# Env_sensor_v1_0.net
KiCad netlist of a schematic drawn in EAGLE
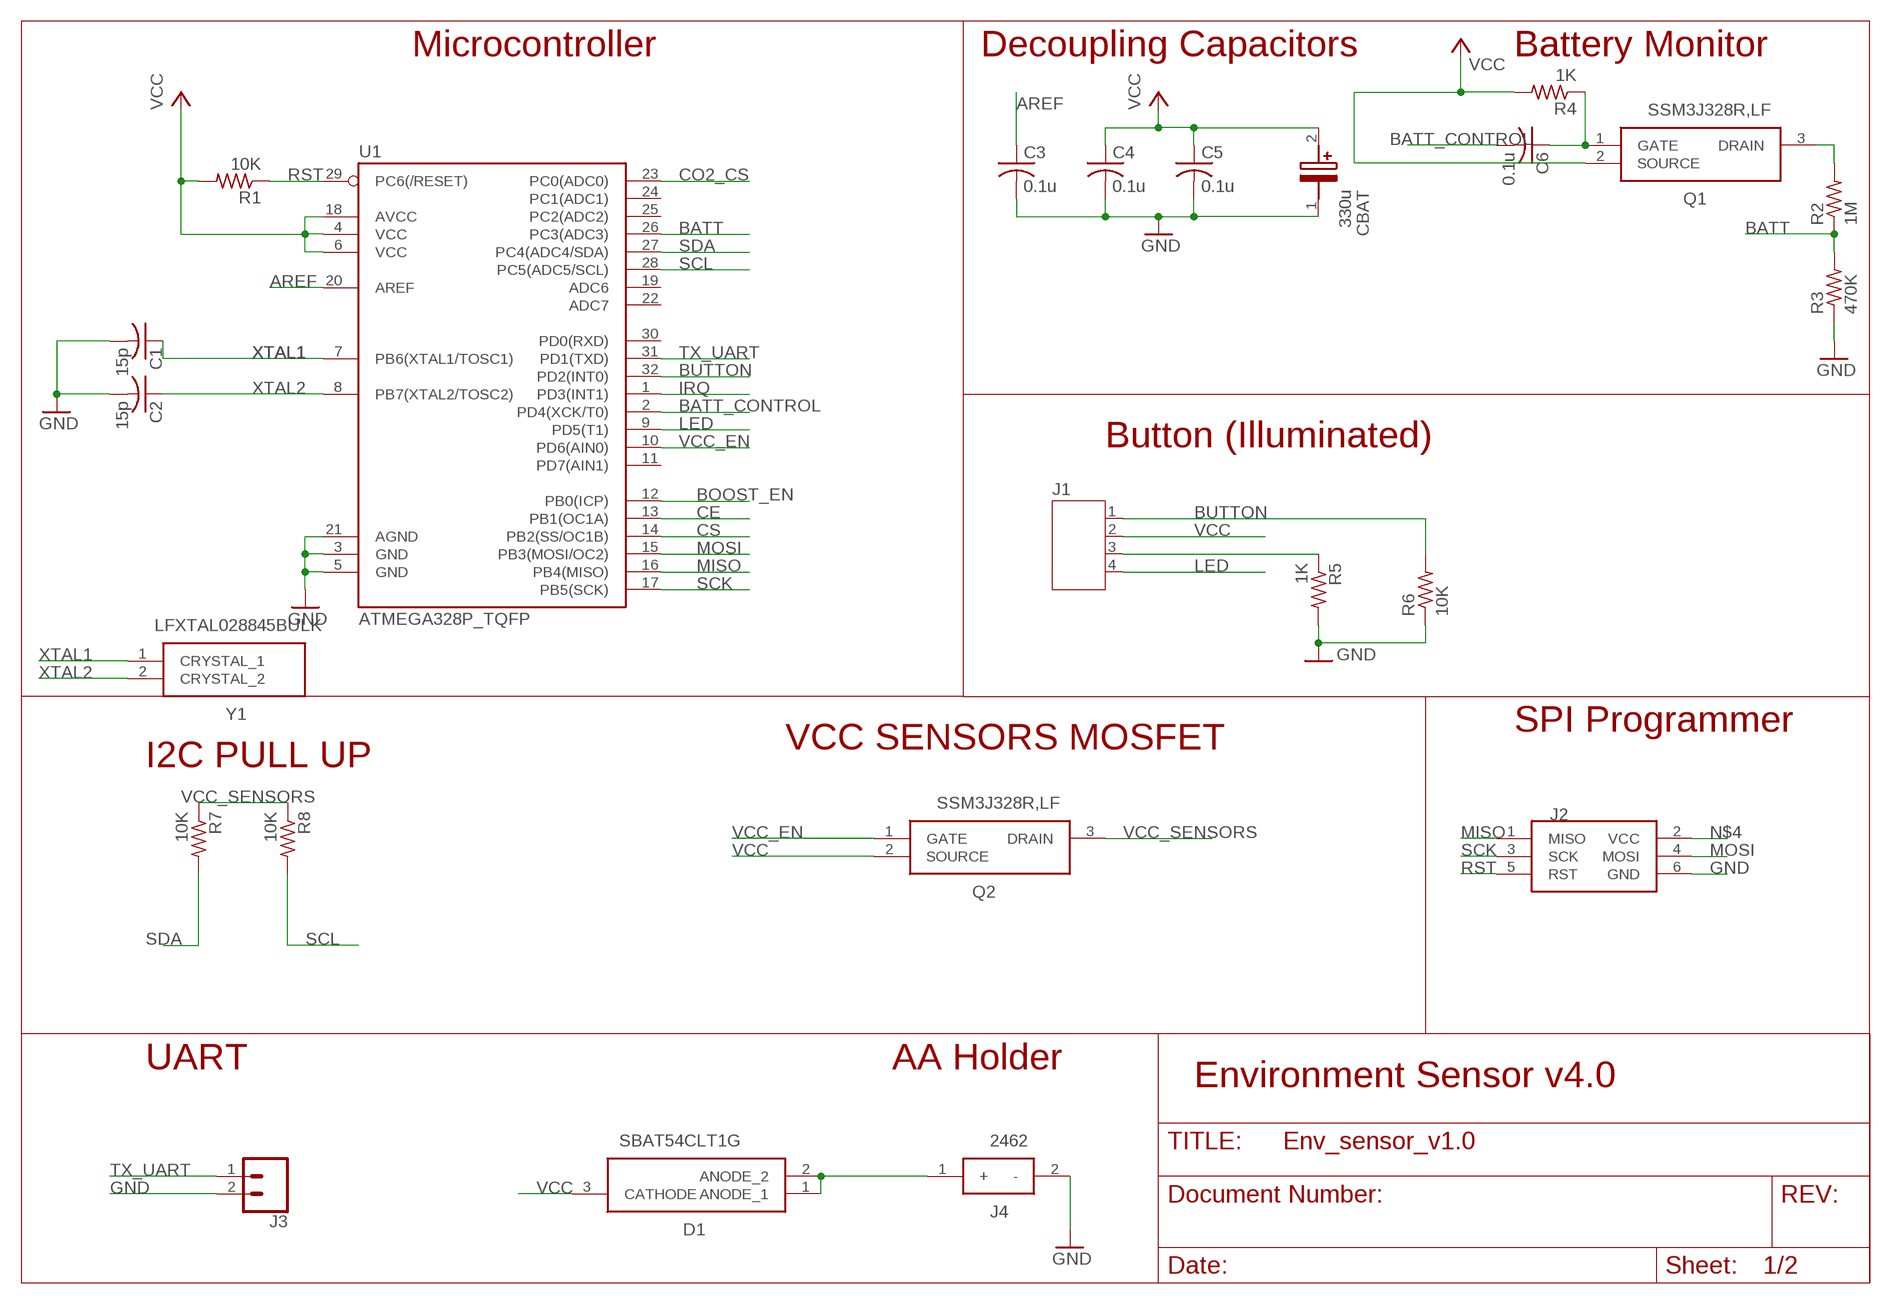
[diagram p0: schematic, sheet 1]
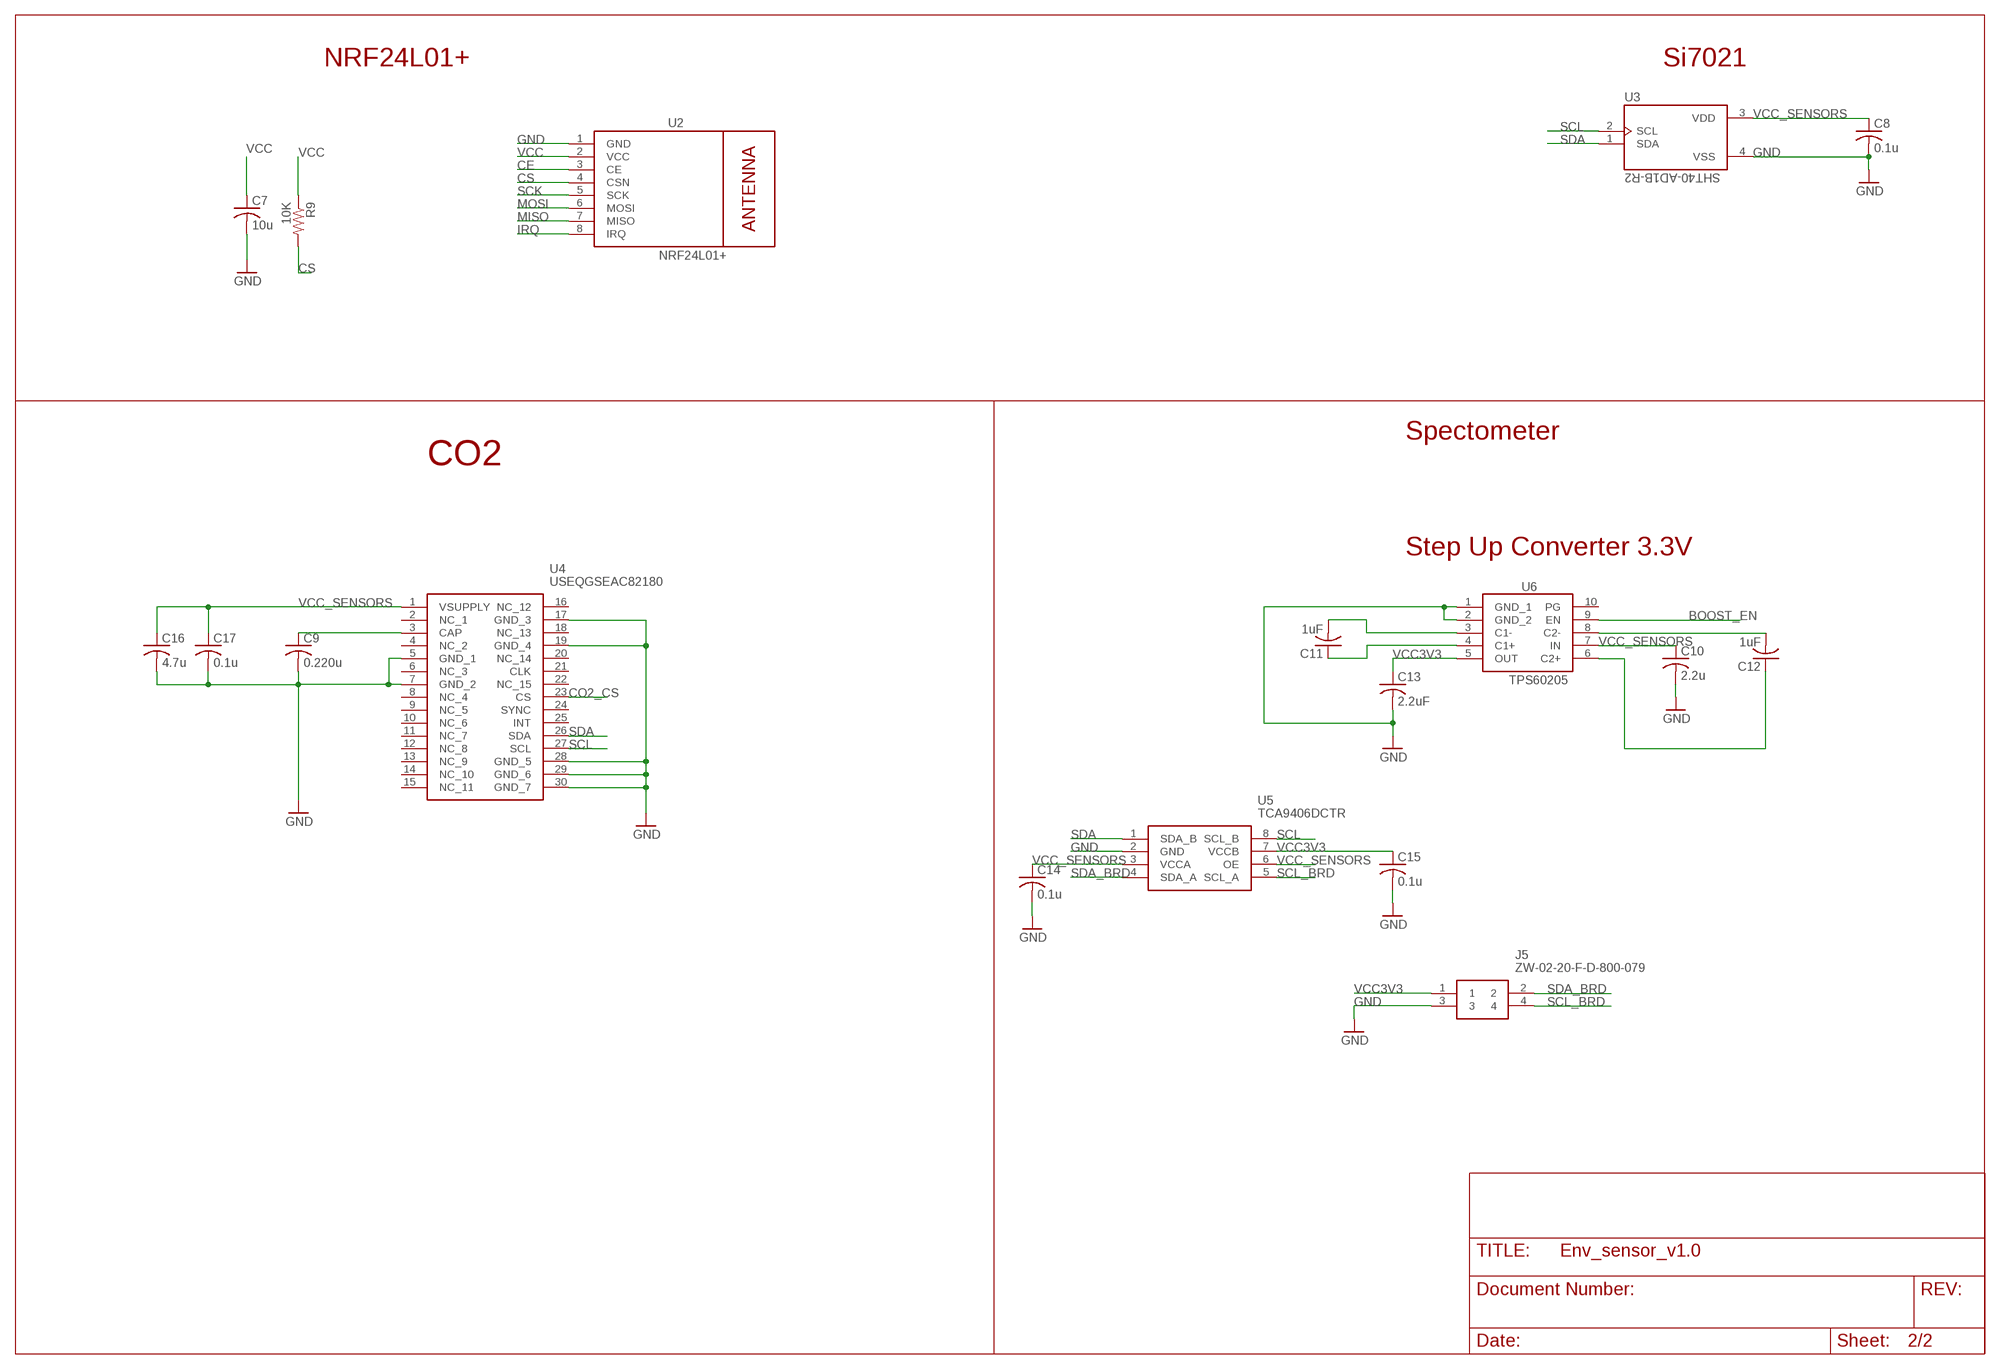
[diagram p1: schematic, sheet 2]

(export (version "E")
  (design (tool "Eeschema 10.0.6"))
  (components
    (comp (ref "C1")
      (value "15p")
      (footprint "eagle-import:SMD-0805")
      (libsource (lib "eagle-import") (part "CAPACITOR-SMD-0805"))
    )
    (comp (ref "C2")
      (value "15p")
      (footprint "eagle-import:SMD-0805")
      (libsource (lib "eagle-import") (part "CAPACITOR-SMD-0805"))
    )
    (comp (ref "C3")
      (value "0.1u")
      (footprint "eagle-import:SMD-0805")
      (libsource (lib "eagle-import") (part "CAPACITOR-SMD-0805"))
    )
    (comp (ref "C4")
      (value "0.1u")
      (footprint "eagle-import:SMD-0805")
      (libsource (lib "eagle-import") (part "CAPACITOR-SMD-0805"))
    )
    (comp (ref "C5")
      (value "0.1u")
      (footprint "eagle-import:SMD-0805")
      (libsource (lib "eagle-import") (part "CAPACITOR-SMD-0805"))
    )
    (comp (ref "C6")
      (value "0.1u")
      (footprint "eagle-import:SMD-0805")
      (libsource (lib "eagle-import") (part "CAPACITOR-SMD-0805"))
    )
    (comp (ref "CBAT")
      (value "330u")
      (footprint "eagle-import:SMD_LYTIC_D8")
      (fields
        (field (name "MANUFACTURER_PART_NUMBER") "EEE-FNC271XUP")
        (field (name "MOUSER_PART_NUMBER") "667-EEE-FNC271XUP")
      )
      (libsource (lib "eagle-import") (part "EEE-FNC271XUP"))
    )
    (comp (ref "D1")
      (value "SBAT54CLT1G")
      (footprint "eagle-import:SOT96P237X111-3N")
      (fields (field (name "MOUSER_PART_NUMBER") "863-SBAT54CLT1G"))
      (libsource (lib "eagle-import") (part "SBAT54CLT1G"))
    )
    (comp (ref "J1")
      (value "JST-PH4")
      (footprint "eagle-import:JST-PH4")
      (libsource (lib "eagle-import") (part "JST-PH4"))
    )
    (comp (ref "J2")
      (value "ISP")
      (footprint "eagle-import:AVRISP")
      (libsource (lib "eagle-import") (part "AVRISP-6"))
    )
    (comp (ref "J3")
      (value "CONN_02")
      (footprint "eagle-import:1X02")
      (libsource (lib "eagle-import") (part "CONN_02"))
    )
    (comp (ref "J4")
      (value "2462")
      (footprint "eagle-import:2462")
      (fields (field (name "MOUSER_PART_NUMBER") "534-2462"))
      (libsource (lib "eagle-import") (part "2462"))
    )
    (comp (ref "Q1")
      (value "SSM3J328R,LF")
      (footprint "eagle-import:SOTFL95P240X88-3N")
      (fields (field (name "MOUSER_PART_NUMBER") "757-SSM3J328RLF"))
      (libsource (lib "eagle-import") (part "SSM3J328R,LF"))
    )
    (comp (ref "Q2")
      (value "SSM3J328R,LF")
      (footprint "eagle-import:SOTFL95P240X88-3N")
      (fields (field (name "MOUSER_PART_NUMBER") "757-SSM3J328RLF"))
      (libsource (lib "eagle-import") (part "SSM3J328R,LF"))
    )
    (comp (ref "R1")
      (value "10K")
      (footprint "eagle-import:SMD-0805")
      (libsource (lib "eagle-import") (part "RESISTOR-SMD-0805"))
    )
    (comp (ref "R2")
      (value "1M")
      (footprint "eagle-import:SMD-0805")
      (libsource (lib "eagle-import") (part "RESISTOR-SMD-0805"))
    )
    (comp (ref "R3")
      (value "470K")
      (footprint "eagle-import:SMD-0805")
      (libsource (lib "eagle-import") (part "RESISTOR-SMD-0805"))
    )
    (comp (ref "R4")
      (value "1K")
      (footprint "eagle-import:SMD-0805")
      (libsource (lib "eagle-import") (part "RESISTOR-SMD-0805"))
    )
    (comp (ref "R5")
      (value "1K")
      (footprint "eagle-import:SMD-0805")
      (libsource (lib "eagle-import") (part "RESISTOR-SMD-0805"))
    )
    (comp (ref "R6")
      (value "10K")
      (footprint "eagle-import:SMD-0805")
      (libsource (lib "eagle-import") (part "RESISTOR-SMD-0805"))
    )
    (comp (ref "R7")
      (value "10K")
      (footprint "eagle-import:SMD-0805")
      (libsource (lib "eagle-import") (part "RESISTOR-SMD-0805"))
    )
    (comp (ref "R8")
      (value "10K")
      (footprint "eagle-import:SMD-0805")
      (libsource (lib "eagle-import") (part "RESISTOR-SMD-0805"))
    )
    (comp (ref "U1")
      (value "ATMEGA328P_TQFP")
      (footprint "eagle-import:TQFP32-08")
      (libsource (lib "eagle-import") (part "ATMEGA328P_TQFP"))
    )
    (comp (ref "Y1")
      (value "LFXTAL028845BULK")
      (footprint "eagle-import:LFXTAL028845BULK")
      (libsource (lib "eagle-import") (part "LFXTAL028845BULK"))
    )
    (comp (ref "C7")
      (value "10u")
      (footprint "eagle-import:SMD-0805")
      (libsource (lib "eagle-import") (part "CAPACITOR-SMD-0805"))
    )
    (comp (ref "C8")
      (value "0.1u")
      (footprint "eagle-import:SMD-0805")
      (libsource (lib "eagle-import") (part "CAPACITOR-SMD-0805"))
    )
    (comp (ref "C9")
      (value "0.220u")
      (footprint "eagle-import:SMD-0805")
      (libsource (lib "eagle-import") (part "CAPACITOR-SMD-0805"))
    )
    (comp (ref "C10")
      (value "2.2u")
      (footprint "eagle-import:SMD-0805")
      (libsource (lib "eagle-import") (part "CAPACITOR-SMD-0805"))
    )
    (comp (ref "C11")
      (value "1uF")
      (footprint "eagle-import:SMD-0805")
      (libsource (lib "eagle-import") (part "CAPACITOR-SMD-0805"))
    )
    (comp (ref "C12")
      (value "1uF")
      (footprint "eagle-import:SMD-0805")
      (libsource (lib "eagle-import") (part "CAPACITOR-SMD-0805"))
    )
    (comp (ref "C13")
      (value "2.2uF")
      (footprint "eagle-import:SMD-0805")
      (libsource (lib "eagle-import") (part "CAPACITOR-SMD-0805"))
    )
    (comp (ref "C14")
      (value "0.1u")
      (footprint "eagle-import:SMD-0805")
      (libsource (lib "eagle-import") (part "CAPACITOR-SMD-0805"))
    )
    (comp (ref "C15")
      (value "0.1u")
      (footprint "eagle-import:SMD-0805")
      (libsource (lib "eagle-import") (part "CAPACITOR-SMD-0805"))
    )
    (comp (ref "C16")
      (value "4.7u")
      (footprint "eagle-import:SMD-0805")
      (libsource (lib "eagle-import") (part "CAPACITOR-SMD-0805"))
    )
    (comp (ref "C17")
      (value "0.1u")
      (footprint "eagle-import:SMD-0805")
      (libsource (lib "eagle-import") (part "CAPACITOR-SMD-0805"))
    )
    (comp (ref "J5")
      (value "ZW-02-20-F-D-800-079")
      (footprint "eagle-import:HDRV4W64P254_2X2_508X508X2669P")
      (fields (field (name "MOUSER_PART_NUMBER") "200-ZW0220FD800079"))
      (libsource (lib "eagle-import") (part "ZW-02-20-F-D-800-079"))
    )
    (comp (ref "R9")
      (value "10K")
      (footprint "eagle-import:SMD-0805")
      (libsource (lib "eagle-import") (part "RESISTOR-SMD-0805"))
    )
    (comp (ref "U2")
      (value "NRF24L01+")
      (footprint "eagle-import:WIRELESS-NRF24L01")
      (libsource (lib "eagle-import") (part "WIRELESS-NRF24L01"))
    )
    (comp (ref "U3")
      (value "SHT40-AD1B-R2")
      (footprint "eagle-import:XDCR_SHT40-AD1B-R2")
      (fields (field (name "MF") "Sensirion"))
      (libsource (lib "eagle-import") (part "SHT40-AD1B-R2"))
    )
    (comp (ref "U4")
      (value "USEQGSEAC82180")
      (footprint "eagle-import:USEQGSEAC82180")
      (fields (field (name "MOUSER_PART_NUMBER") "80-USEQGSEAC82180"))
      (libsource (lib "eagle-import") (part "USEQGSEAC82180"))
    )
    (comp (ref "U5")
      (value "TCA9406DCTR")
      (footprint "eagle-import:SOP65P400X130-8N")
      (fields (field (name "MOUSER_PART_NUMBER") "595-TCA9406DCTR"))
      (libsource (lib "eagle-import") (part "TCA9406DCTR"))
    )
    (comp (ref "U6")
      (value "TPS60205")
      (footprint "eagle-import:SOP50P488X107-10N")
      (fields
        (field (name "MANUFACTURER_PART_NUMBER") "TPS60205DGSR")
        (field (name "MOUSER_PART_NUMBER") "595-TPS60205DGSR")
      )
      (libsource (lib "eagle-import") (part "TPS60205DGSR"))
    )
  )
  (nets
    (net (code "1") (name "AREF") (class "Default")
      (node (ref "C3") (pin "1") (pinfunction "1_1") (pintype "passive"))
      (node (ref "U1") (pin "20") (pinfunction "AREF_20") (pintype "bidirectional"))
    )
    (net (code "2") (name "BATT") (class "Default")
      (node (ref "R2") (pin "1") (pinfunction "1_1") (pintype "passive"))
      (node (ref "R3") (pin "2") (pinfunction "2_2") (pintype "passive"))
      (node (ref "U1") (pin "26") (pinfunction "PC3(ADC3)_26") (pintype "bidirectional"))
    )
    (net (code "3") (name "BATT_CONTROL") (class "Default")
      (node (ref "C6") (pin "2") (pinfunction "2_2") (pintype "passive"))
      (node (ref "U1") (pin "2") (pinfunction "PD4(XCK/T0)_2") (pintype "bidirectional"))
    )
    (net (code "4") (name "BOOST_EN") (class "Default")
      (node (ref "U1") (pin "12") (pinfunction "PB0(ICP)_12") (pintype "bidirectional"))
      (node (ref "U6") (pin "9") (pinfunction "EN_9") (pintype "bidirectional"))
    )
    (net (code "5") (name "BUTTON") (class "Default")
      (node (ref "J1") (pin "1") (pinfunction "1_1") (pintype "passive"))
      (node (ref "R6") (pin "2") (pinfunction "2_2") (pintype "passive"))
      (node (ref "U1") (pin "32") (pinfunction "PD2(INT0)_32") (pintype "bidirectional"))
    )
    (net (code "6") (name "CE") (class "Default")
      (node (ref "U1") (pin "13") (pinfunction "PB1(OC1A)_13") (pintype "bidirectional"))
      (node (ref "U2") (pin "3") (pinfunction "CE_3") (pintype "bidirectional"))
    )
    (net (code "7") (name "CO2_CS") (class "Default")
      (node (ref "U1") (pin "23") (pinfunction "PC0(ADC0)_23") (pintype "bidirectional"))
      (node (ref "U4") (pin "23") (pinfunction "CS_23") (pintype "bidirectional"))
    )
    (net (code "8") (name "CS") (class "Default")
      (node (ref "R9") (pin "2") (pinfunction "2_2") (pintype "passive"))
      (node (ref "U1") (pin "14") (pinfunction "PB2(SS/OC1B)_14") (pintype "bidirectional"))
      (node (ref "U2") (pin "4") (pinfunction "CSN_4") (pintype "bidirectional"))
    )
    (net (code "9") (name "GND") (class "Default")
      (node (ref "C1") (pin "2") (pinfunction "2_2") (pintype "passive"))
      (node (ref "C10") (pin "2") (pinfunction "2_2") (pintype "passive"))
      (node (ref "C13") (pin "2") (pinfunction "2_2") (pintype "passive"))
      (node (ref "C14") (pin "2") (pinfunction "2_2") (pintype "passive"))
      (node (ref "C15") (pin "2") (pinfunction "2_2") (pintype "passive"))
      (node (ref "C16") (pin "2") (pinfunction "2_2") (pintype "passive"))
      (node (ref "C17") (pin "2") (pinfunction "2_2") (pintype "passive"))
      (node (ref "C2") (pin "2") (pinfunction "2_2") (pintype "passive"))
      (node (ref "C3") (pin "2") (pinfunction "2_2") (pintype "passive"))
      (node (ref "C4") (pin "2") (pinfunction "2_2") (pintype "passive"))
      (node (ref "C5") (pin "2") (pinfunction "2_2") (pintype "passive"))
      (node (ref "C7") (pin "2") (pinfunction "2_2") (pintype "passive"))
      (node (ref "C8") (pin "2") (pinfunction "2_2") (pintype "passive"))
      (node (ref "C9") (pin "2") (pinfunction "2_2") (pintype "passive"))
      (node (ref "CBAT") (pin "1") (pinfunction "1_1") (pintype "bidirectional"))
      (node (ref "J2") (pin "6") (pinfunction "GND_6") (pintype "power_in"))
      (node (ref "J3") (pin "2") (pinfunction "2_2") (pintype "passive"))
      (node (ref "J4") (pin "2") (pinfunction "-_2") (pintype "bidirectional"))
      (node (ref "J5") (pin "3") (pinfunction "3_3") (pintype "bidirectional"))
      (node (ref "R3") (pin "1") (pinfunction "1_1") (pintype "passive"))
      (node (ref "R5") (pin "2") (pinfunction "2_2") (pintype "passive"))
      (node (ref "R6") (pin "1") (pinfunction "1_1") (pintype "passive"))
      (node (ref "U1") (pin "21") (pinfunction "AGND_21") (pintype "bidirectional"))
      (node (ref "U1") (pin "3") (pinfunction "GND_3") (pintype "bidirectional"))
      (node (ref "U1") (pin "5") (pinfunction "GND_5") (pintype "bidirectional"))
      (node (ref "U2") (pin "1") (pinfunction "GND_1") (pintype "power_in"))
      (node (ref "U3") (pin "4") (pinfunction "VSS_4") (pintype "power_in"))
      (node (ref "U4") (pin "17") (pinfunction "GND_3_17") (pintype "bidirectional"))
      (node (ref "U4") (pin "19") (pinfunction "GND_4_19") (pintype "bidirectional"))
      (node (ref "U4") (pin "28") (pinfunction "GND_5_28") (pintype "bidirectional"))
      (node (ref "U4") (pin "29") (pinfunction "GND_6_29") (pintype "bidirectional"))
      (node (ref "U4") (pin "30") (pinfunction "GND_7_30") (pintype "bidirectional"))
      (node (ref "U4") (pin "5") (pinfunction "GND_1_5") (pintype "bidirectional"))
      (node (ref "U4") (pin "7") (pinfunction "GND_2_7") (pintype "bidirectional"))
      (node (ref "U5") (pin "2") (pinfunction "GND_2") (pintype "bidirectional"))
      (node (ref "U6") (pin "1") (pinfunction "GND_1_1") (pintype "bidirectional"))
      (node (ref "U6") (pin "2") (pinfunction "GND_2_2") (pintype "bidirectional"))
    )
    (net (code "10") (name "IRQ") (class "Default")
      (node (ref "U1") (pin "1") (pinfunction "PD3(INT1)_1") (pintype "bidirectional"))
      (node (ref "U2") (pin "8") (pinfunction "IRQ_8") (pintype "bidirectional"))
    )
    (net (code "11") (name "LED") (class "Default")
      (node (ref "J1") (pin "4") (pinfunction "4_4") (pintype "passive"))
      (node (ref "U1") (pin "9") (pinfunction "PD5(T1)_9") (pintype "bidirectional"))
    )
    (net (code "12") (name "MISO") (class "Default")
      (node (ref "J2") (pin "1") (pinfunction "MISO_1") (pintype "input"))
      (node (ref "U1") (pin "16") (pinfunction "PB4(MISO)_16") (pintype "bidirectional"))
      (node (ref "U2") (pin "7") (pinfunction "MISO_7") (pintype "bidirectional"))
    )
    (net (code "13") (name "MOSI") (class "Default")
      (node (ref "J2") (pin "4") (pinfunction "MOSI_4") (pintype "output"))
      (node (ref "U1") (pin "15") (pinfunction "PB3(MOSI/OC2)_15") (pintype "bidirectional"))
      (node (ref "U2") (pin "6") (pinfunction "MOSI_6") (pintype "bidirectional"))
    )
    (net (code "14") (name "N$4") (class "Default")
      (node (ref "J2") (pin "2") (pinfunction "VCC_2") (pintype "power_in"))
    )
    (net (code "15") (name "Net-(D1-ANODE_1)") (class "Default")
      (node (ref "D1") (pin "1") (pinfunction "ANODE_1_1") (pintype "bidirectional"))
      (node (ref "D1") (pin "2") (pinfunction "ANODE_2_2") (pintype "bidirectional"))
      (node (ref "J4") (pin "1") (pinfunction "+_1") (pintype "bidirectional"))
    )
    (net (code "16") (name "Net-(J1-Pad3)") (class "Default")
      (node (ref "J1") (pin "3") (pinfunction "3_3") (pintype "passive"))
      (node (ref "R5") (pin "1") (pinfunction "1_1") (pintype "passive"))
    )
    (net (code "17") (name "Net-(Q1-DRAIN)") (class "Default")
      (node (ref "Q1") (pin "3") (pinfunction "DRAIN_3") (pintype "bidirectional"))
      (node (ref "R2") (pin "2") (pinfunction "2_2") (pintype "passive"))
    )
    (net (code "18") (name "Net-(Q1-GATE)") (class "Default")
      (node (ref "C6") (pin "1") (pinfunction "1_1") (pintype "passive"))
      (node (ref "Q1") (pin "1") (pinfunction "GATE_1") (pintype "input"))
      (node (ref "R4") (pin "1") (pinfunction "1_1") (pintype "passive"))
    )
    (net (code "19") (name "Net-(U4-CAP)") (class "Default")
      (node (ref "C9") (pin "1") (pinfunction "1_1") (pintype "passive"))
      (node (ref "U4") (pin "3") (pinfunction "CAP_3") (pintype "bidirectional"))
    )
    (net (code "20") (name "Net-(U6-C1+)") (class "Default")
      (node (ref "C11") (pin "1") (pinfunction "1_1") (pintype "passive"))
      (node (ref "U6") (pin "4") (pinfunction "C1+_4") (pintype "bidirectional"))
    )
    (net (code "21") (name "Net-(U6-C1-)") (class "Default")
      (node (ref "C11") (pin "2") (pinfunction "2_2") (pintype "passive"))
      (node (ref "U6") (pin "3") (pinfunction "C1-_3") (pintype "bidirectional"))
    )
    (net (code "22") (name "Net-(U6-C2+)") (class "Default")
      (node (ref "C12") (pin "1") (pinfunction "1_1") (pintype "passive"))
      (node (ref "U6") (pin "6") (pinfunction "C2+_6") (pintype "bidirectional"))
    )
    (net (code "23") (name "Net-(U6-C2-)") (class "Default")
      (node (ref "C12") (pin "2") (pinfunction "2_2") (pintype "passive"))
      (node (ref "U6") (pin "8") (pinfunction "C2-_8") (pintype "bidirectional"))
    )
    (net (code "24") (name "RST") (class "Default")
      (node (ref "J2") (pin "5") (pinfunction "RST_5") (pintype "output"))
      (node (ref "R1") (pin "1") (pinfunction "1_1") (pintype "passive"))
      (node (ref "U1") (pin "29") (pinfunction "PC6(/RESET)_29") (pintype "bidirectional"))
    )
    (net (code "25") (name "SCK") (class "Default")
      (node (ref "J2") (pin "3") (pinfunction "SCK_3") (pintype "output"))
      (node (ref "U1") (pin "17") (pinfunction "PB5(SCK)_17") (pintype "bidirectional"))
      (node (ref "U2") (pin "5") (pinfunction "SCK_5") (pintype "bidirectional"))
    )
    (net (code "26") (name "SCL") (class "Default")
      (node (ref "R8") (pin "2") (pinfunction "2_2") (pintype "passive"))
      (node (ref "U1") (pin "28") (pinfunction "PC5(ADC5/SCL)_28") (pintype "bidirectional"))
      (node (ref "U3") (pin "2") (pinfunction "SCL_2") (pintype "input"))
      (node (ref "U4") (pin "27") (pinfunction "SCL_27") (pintype "bidirectional"))
      (node (ref "U5") (pin "8") (pinfunction "SCL_B_8") (pintype "bidirectional"))
    )
    (net (code "27") (name "SCL_BRD") (class "Default")
      (node (ref "J5") (pin "4") (pinfunction "4_4") (pintype "bidirectional"))
      (node (ref "U5") (pin "5") (pinfunction "SCL_A_5") (pintype "bidirectional"))
    )
    (net (code "28") (name "SDA") (class "Default")
      (node (ref "R7") (pin "2") (pinfunction "2_2") (pintype "passive"))
      (node (ref "U1") (pin "27") (pinfunction "PC4(ADC4/SDA)_27") (pintype "bidirectional"))
      (node (ref "U3") (pin "1") (pinfunction "SDA_1") (pintype "bidirectional"))
      (node (ref "U4") (pin "26") (pinfunction "SDA_26") (pintype "bidirectional"))
      (node (ref "U5") (pin "1") (pinfunction "SDA_B_1") (pintype "bidirectional"))
    )
    (net (code "29") (name "SDA_BRD") (class "Default")
      (node (ref "J5") (pin "2") (pinfunction "2_2") (pintype "bidirectional"))
      (node (ref "U5") (pin "4") (pinfunction "SDA_A_4") (pintype "bidirectional"))
    )
    (net (code "30") (name "TX_UART") (class "Default")
      (node (ref "J3") (pin "1") (pinfunction "1_1") (pintype "passive"))
      (node (ref "U1") (pin "31") (pinfunction "PD1(TXD)_31") (pintype "bidirectional"))
    )
    (net (code "31") (name "VCC") (class "Default")
      (node (ref "C4") (pin "1") (pinfunction "1_1") (pintype "passive"))
      (node (ref "C5") (pin "1") (pinfunction "1_1") (pintype "passive"))
      (node (ref "C7") (pin "1") (pinfunction "1_1") (pintype "passive"))
      (node (ref "CBAT") (pin "2") (pinfunction "2_2") (pintype "bidirectional"))
      (node (ref "D1") (pin "3") (pinfunction "CATHODE_3") (pintype "bidirectional"))
      (node (ref "J1") (pin "2") (pinfunction "2_2") (pintype "passive"))
      (node (ref "Q1") (pin "2") (pinfunction "SOURCE_2") (pintype "bidirectional"))
      (node (ref "Q2") (pin "2") (pinfunction "SOURCE_2") (pintype "bidirectional"))
      (node (ref "R1") (pin "2") (pinfunction "2_2") (pintype "passive"))
      (node (ref "R4") (pin "2") (pinfunction "2_2") (pintype "passive"))
      (node (ref "R9") (pin "1") (pinfunction "1_1") (pintype "passive"))
      (node (ref "U1") (pin "18") (pinfunction "AVCC_18") (pintype "bidirectional"))
      (node (ref "U1") (pin "4") (pinfunction "VCC_4") (pintype "bidirectional"))
      (node (ref "U1") (pin "6") (pinfunction "VCC_6") (pintype "bidirectional"))
      (node (ref "U2") (pin "2") (pinfunction "VCC_2") (pintype "power_in"))
    )
    (net (code "32") (name "VCC3V3") (class "Default")
      (node (ref "C13") (pin "1") (pinfunction "1_1") (pintype "passive"))
      (node (ref "C15") (pin "1") (pinfunction "1_1") (pintype "passive"))
      (node (ref "J5") (pin "1") (pinfunction "1_1") (pintype "bidirectional"))
      (node (ref "U5") (pin "7") (pinfunction "VCCB_7") (pintype "bidirectional"))
      (node (ref "U6") (pin "5") (pinfunction "OUT_5") (pintype "bidirectional"))
    )
    (net (code "33") (name "VCC_EN") (class "Default")
      (node (ref "Q2") (pin "1") (pinfunction "GATE_1") (pintype "input"))
      (node (ref "U1") (pin "10") (pinfunction "PD6(AIN0)_10") (pintype "bidirectional"))
    )
    (net (code "34") (name "VCC_SENSORS") (class "Default")
      (node (ref "C10") (pin "1") (pinfunction "1_1") (pintype "passive"))
      (node (ref "C14") (pin "1") (pinfunction "1_1") (pintype "passive"))
      (node (ref "C16") (pin "1") (pinfunction "1_1") (pintype "passive"))
      (node (ref "C17") (pin "1") (pinfunction "1_1") (pintype "passive"))
      (node (ref "C8") (pin "1") (pinfunction "1_1") (pintype "passive"))
      (node (ref "Q2") (pin "3") (pinfunction "DRAIN_3") (pintype "bidirectional"))
      (node (ref "R7") (pin "1") (pinfunction "1_1") (pintype "passive"))
      (node (ref "R8") (pin "1") (pinfunction "1_1") (pintype "passive"))
      (node (ref "U3") (pin "3") (pinfunction "VDD_3") (pintype "power_in"))
      (node (ref "U4") (pin "1") (pinfunction "VSUPPLY_1") (pintype "bidirectional"))
      (node (ref "U5") (pin "3") (pinfunction "VCCA_3") (pintype "bidirectional"))
      (node (ref "U5") (pin "6") (pinfunction "OE_6") (pintype "bidirectional"))
      (node (ref "U6") (pin "7") (pinfunction "IN_7") (pintype "bidirectional"))
    )
    (net (code "35") (name "XTAL1") (class "Default")
      (node (ref "C1") (pin "1") (pinfunction "1_1") (pintype "passive"))
      (node (ref "U1") (pin "7") (pinfunction "PB6(XTAL1/TOSC1)_7") (pintype "bidirectional"))
      (node (ref "Y1") (pin "1") (pinfunction "CRYSTAL_1_1") (pintype "bidirectional"))
    )
    (net (code "36") (name "XTAL2") (class "Default")
      (node (ref "C2") (pin "1") (pinfunction "1_1") (pintype "passive"))
      (node (ref "U1") (pin "8") (pinfunction "PB7(XTAL2/TOSC2)_8") (pintype "bidirectional"))
      (node (ref "Y1") (pin "2") (pinfunction "CRYSTAL_2_2") (pintype "bidirectional"))
    )
    (net (code "37") (name "unconnected-(U1-ADC6-Pad19)") (class "Default")
      (node (ref "U1") (pin "19") (pinfunction "ADC6_19") (pintype "bidirectional"))
    )
    (net (code "38") (name "unconnected-(U1-ADC7-Pad22)") (class "Default")
      (node (ref "U1") (pin "22") (pinfunction "ADC7_22") (pintype "bidirectional"))
    )
    (net (code "39") (name "unconnected-(U1-PC1(ADC1)-Pad24)") (class "Default")
      (node (ref "U1") (pin "24") (pinfunction "PC1(ADC1)_24") (pintype "bidirectional"))
    )
    (net (code "40") (name "unconnected-(U1-PC2(ADC2)-Pad25)") (class "Default")
      (node (ref "U1") (pin "25") (pinfunction "PC2(ADC2)_25") (pintype "bidirectional"))
    )
    (net (code "41") (name "unconnected-(U1-PD0(RXD)-Pad30)") (class "Default")
      (node (ref "U1") (pin "30") (pinfunction "PD0(RXD)_30") (pintype "bidirectional"))
    )
    (net (code "42") (name "unconnected-(U1-PD7(AIN1)-Pad11)") (class "Default")
      (node (ref "U1") (pin "11") (pinfunction "PD7(AIN1)_11") (pintype "bidirectional"))
    )
    (net (code "43") (name "unconnected-(U4-CLK-Pad21)") (class "Default")
      (node (ref "U4") (pin "21") (pinfunction "CLK_21") (pintype "bidirectional"))
    )
    (net (code "44") (name "unconnected-(U4-INT-Pad25)") (class "Default")
      (node (ref "U4") (pin "25") (pinfunction "INT_25") (pintype "bidirectional"))
    )
    (net (code "45") (name "unconnected-(U4-NC_1-Pad2)") (class "Default")
      (node (ref "U4") (pin "2") (pinfunction "NC_1_2") (pintype "bidirectional"))
    )
    (net (code "46") (name "unconnected-(U4-NC_2-Pad4)") (class "Default")
      (node (ref "U4") (pin "4") (pinfunction "NC_2_4") (pintype "bidirectional"))
    )
    (net (code "47") (name "unconnected-(U4-NC_3-Pad6)") (class "Default")
      (node (ref "U4") (pin "6") (pinfunction "NC_3_6") (pintype "bidirectional"))
    )
    (net (code "48") (name "unconnected-(U4-NC_4-Pad8)") (class "Default")
      (node (ref "U4") (pin "8") (pinfunction "NC_4_8") (pintype "bidirectional"))
    )
    (net (code "49") (name "unconnected-(U4-NC_5-Pad9)") (class "Default")
      (node (ref "U4") (pin "9") (pinfunction "NC_5_9") (pintype "bidirectional"))
    )
    (net (code "50") (name "unconnected-(U4-NC_6-Pad10)") (class "Default")
      (node (ref "U4") (pin "10") (pinfunction "NC_6_10") (pintype "bidirectional"))
    )
    (net (code "51") (name "unconnected-(U4-NC_7-Pad11)") (class "Default")
      (node (ref "U4") (pin "11") (pinfunction "NC_7_11") (pintype "bidirectional"))
    )
    (net (code "52") (name "unconnected-(U4-NC_8-Pad12)") (class "Default")
      (node (ref "U4") (pin "12") (pinfunction "NC_8_12") (pintype "bidirectional"))
    )
    (net (code "53") (name "unconnected-(U4-NC_9-Pad13)") (class "Default")
      (node (ref "U4") (pin "13") (pinfunction "NC_9_13") (pintype "bidirectional"))
    )
    (net (code "54") (name "unconnected-(U4-NC_10-Pad14)") (class "Default")
      (node (ref "U4") (pin "14") (pinfunction "NC_10_14") (pintype "bidirectional"))
    )
    (net (code "55") (name "unconnected-(U4-NC_11-Pad15)") (class "Default")
      (node (ref "U4") (pin "15") (pinfunction "NC_11_15") (pintype "bidirectional"))
    )
    (net (code "56") (name "unconnected-(U4-NC_12-Pad16)") (class "Default")
      (node (ref "U4") (pin "16") (pinfunction "NC_12_16") (pintype "bidirectional"))
    )
    (net (code "57") (name "unconnected-(U4-NC_13-Pad18)") (class "Default")
      (node (ref "U4") (pin "18") (pinfunction "NC_13_18") (pintype "bidirectional"))
    )
    (net (code "58") (name "unconnected-(U4-NC_14-Pad20)") (class "Default")
      (node (ref "U4") (pin "20") (pinfunction "NC_14_20") (pintype "bidirectional"))
    )
    (net (code "59") (name "unconnected-(U4-NC_15-Pad22)") (class "Default")
      (node (ref "U4") (pin "22") (pinfunction "NC_15_22") (pintype "bidirectional"))
    )
    (net (code "60") (name "unconnected-(U4-SYNC-Pad24)") (class "Default")
      (node (ref "U4") (pin "24") (pinfunction "SYNC_24") (pintype "bidirectional"))
    )
    (net (code "61") (name "unconnected-(U6-PG-Pad10)") (class "Default")
      (node (ref "U6") (pin "10") (pinfunction "PG_10") (pintype "bidirectional"))
    )
  )
)
